# Franzininho.net
KiCad netlist of a schematic drawn in EAGLE
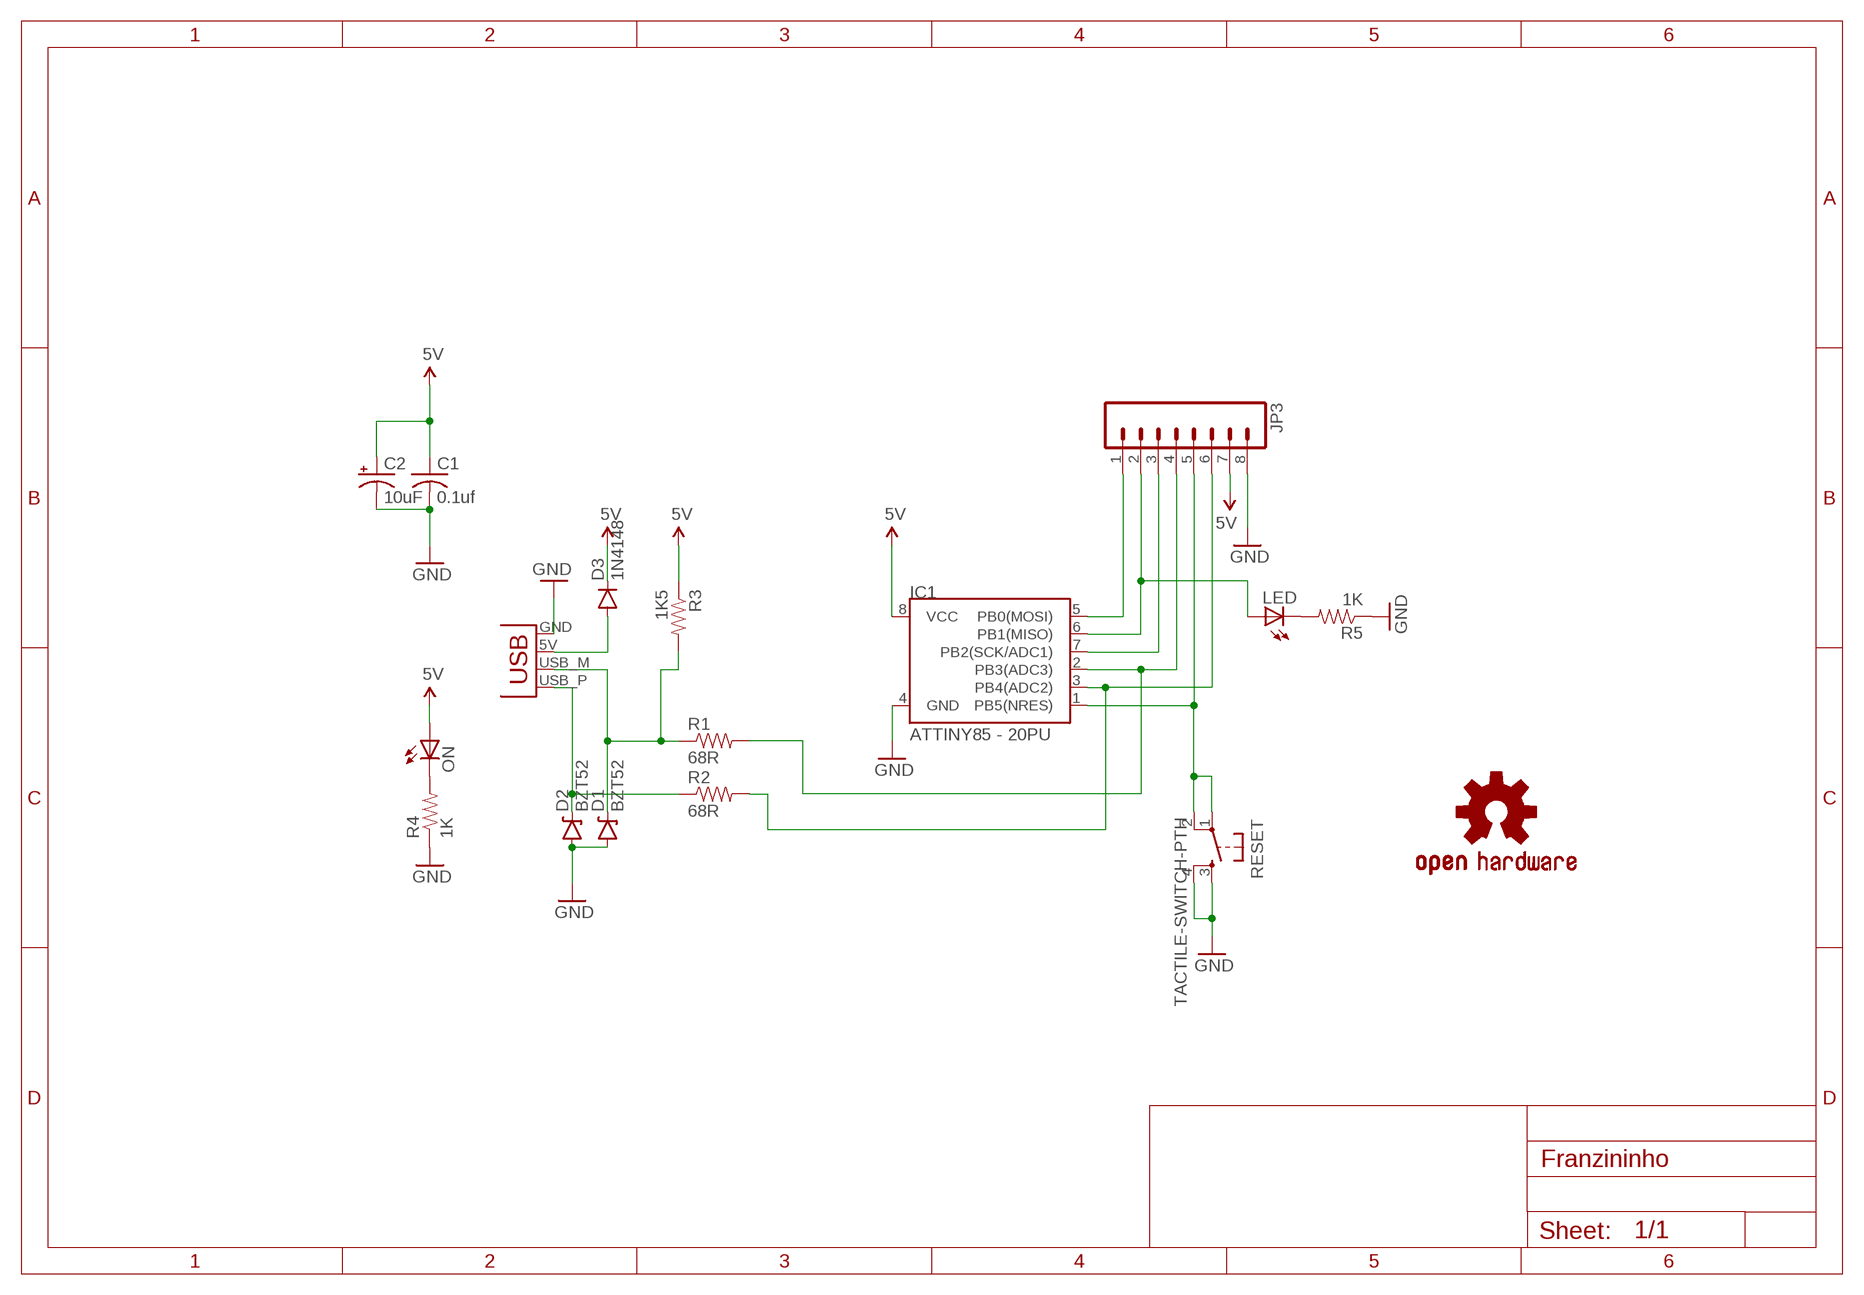
[diagram p0: schematic, sheet 1]

(export (version "E")
  (design (tool "Eeschema 10.0.6"))
  (components
    (comp (ref "C1")
      (value "0.1uf")
      (footprint "eagle-import:C025-025X050")
      (libsource (lib "eagle-import") (part "C-US025-025X050"))
    )
    (comp (ref "C2")
      (value "10uF")
      (footprint "eagle-import:E2,5-6E")
      (libsource (lib "eagle-import") (part "CPOL-USE2,5-6E"))
    )
    (comp (ref "D1")
      (value "BZT52")
      (footprint "eagle-import:DIODE-BZT52")
      (libsource (lib "eagle-import") (part "DIODE-ZENER"))
    )
    (comp (ref "D2")
      (value "BZT52")
      (footprint "eagle-import:DIODE-BZT52")
      (libsource (lib "eagle-import") (part "DIODE-ZENER"))
    )
    (comp (ref "D3")
      (value "1N4148")
      (footprint "eagle-import:DIODE-1N4148")
      (libsource (lib "eagle-import") (part "DIODE1N4148"))
    )
    (comp (ref "IC1")
      (value "ATTINY85 - 20PU")
      (footprint "eagle-import:DIP08")
      (libsource (lib "eagle-import") (part "ATTINY45TINY45-20-DIP"))
    )
    (comp (ref "JP3")
      (value "M08")
      (footprint "eagle-import:1X08_ROUND")
      (libsource (lib "eagle-import") (part "M08"))
    )
    (comp (ref "LED")
      (value "LED3MM")
      (footprint "eagle-import:LED3MM")
      (libsource (lib "eagle-import") (part "LED3MM"))
    )
    (comp (ref "LOGO1")
      (value "OSHW-LOGOL")
      (footprint "eagle-import:OSHW-LOGO-L")
      (libsource (lib "eagle-import") (part "OSHW-LOGOL"))
    )
    (comp (ref "ON")
      (value "LED3MM")
      (footprint "eagle-import:LED3MM")
      (libsource (lib "eagle-import") (part "LED3MM"))
    )
    (comp (ref "R1")
      (value "68R")
      (footprint "eagle-import:AXIAL-0.4")
      (libsource (lib "eagle-import") (part "RESISTORPTH-1/4W"))
    )
    (comp (ref "R2")
      (value "68R")
      (footprint "eagle-import:AXIAL-0.4")
      (libsource (lib "eagle-import") (part "RESISTORPTH-1/4W"))
    )
    (comp (ref "R3")
      (value "1K5")
      (footprint "eagle-import:AXIAL-0.4")
      (libsource (lib "eagle-import") (part "RESISTORPTH-1/4W"))
    )
    (comp (ref "R4")
      (value "1K")
      (footprint "eagle-import:AXIAL-0.4")
      (libsource (lib "eagle-import") (part "RESISTORPTH-1/4W"))
    )
    (comp (ref "R5")
      (value "1K")
      (footprint "eagle-import:AXIAL-0.4")
      (libsource (lib "eagle-import") (part "RESISTORPTH-1/4W"))
    )
    (comp (ref "RESET")
      (value "TACTILE-SWITCH-PTH")
      (footprint "eagle-import:TAC-SWITCH-PTH")
      (libsource (lib "eagle-import") (part "TACTILE-SWITCH-PTH"))
    )
    (comp (ref "X1")
      (value "USBPCB")
      (footprint "eagle-import:USB-A-PCB")
      (libsource (lib "eagle-import") (part "USBPCB"))
    )
  )
  (nets
    (net (code "1") (name "5V") (class "Default")
      (node (ref "C1") (pin "1") (pinfunction "1_1") (pintype "passive"))
      (node (ref "C2") (pin "+") (pinfunction "+_+") (pintype "passive"))
      (node (ref "D3") (pin "C") (pinfunction "C_C") (pintype "passive"))
      (node (ref "IC1") (pin "8") (pinfunction "VCC_8") (pintype "bidirectional"))
      (node (ref "JP3") (pin "7") (pinfunction "7_7") (pintype "passive"))
      (node (ref "ON") (pin "A") (pinfunction "A_A") (pintype "passive"))
      (node (ref "R3") (pin "P$1") (pinfunction "1_P$1") (pintype "passive"))
    )
    (net (code "2") (name "GND") (class "Default")
      (node (ref "C1") (pin "2") (pinfunction "2_2") (pintype "passive"))
      (node (ref "C2") (pin "-") (pinfunction "-_-") (pintype "passive"))
      (node (ref "D1") (pin "A") (pinfunction "A_A") (pintype "passive"))
      (node (ref "D2") (pin "A") (pinfunction "A_A") (pintype "passive"))
      (node (ref "IC1") (pin "4") (pinfunction "GND_4") (pintype "bidirectional"))
      (node (ref "JP3") (pin "8") (pinfunction "8_8") (pintype "passive"))
      (node (ref "R4") (pin "P$1") (pinfunction "1_P$1") (pintype "passive"))
      (node (ref "R5") (pin "P$1") (pinfunction "1_P$1") (pintype "passive"))
      (node (ref "RESET") (pin "3") (pinfunction "3_3") (pintype "passive"))
      (node (ref "RESET") (pin "4") (pinfunction "4_4") (pintype "passive"))
      (node (ref "X1") (pin "GND") (pinfunction "GND_GND") (pintype "bidirectional"))
    )
    (net (code "3") (name "Net-(IC1-PB0(MOSI))") (class "Default")
      (node (ref "IC1") (pin "5") (pinfunction "PB0(MOSI)_5") (pintype "bidirectional"))
      (node (ref "JP3") (pin "1") (pinfunction "1_1") (pintype "passive"))
    )
    (net (code "4") (name "Net-(IC1-PB1(MISO))") (class "Default")
      (node (ref "IC1") (pin "6") (pinfunction "PB1(MISO)_6") (pintype "bidirectional"))
      (node (ref "JP3") (pin "2") (pinfunction "2_2") (pintype "passive"))
      (node (ref "LED") (pin "A") (pinfunction "A_A") (pintype "passive"))
    )
    (net (code "5") (name "Net-(IC1-PB2(SCK{slash}ADC1))") (class "Default")
      (node (ref "IC1") (pin "7") (pinfunction "PB2(SCK/ADC1)_7") (pintype "bidirectional"))
      (node (ref "JP3") (pin "3") (pinfunction "3_3") (pintype "passive"))
    )
    (net (code "6") (name "Net-(IC1-PB3(ADC3))") (class "Default")
      (node (ref "IC1") (pin "2") (pinfunction "PB3(ADC3)_2") (pintype "bidirectional"))
      (node (ref "JP3") (pin "4") (pinfunction "4_4") (pintype "passive"))
      (node (ref "R1") (pin "P$2") (pinfunction "2_P$2") (pintype "passive"))
    )
    (net (code "7") (name "Net-(IC1-PB4(ADC2))") (class "Default")
      (node (ref "IC1") (pin "3") (pinfunction "PB4(ADC2)_3") (pintype "bidirectional"))
      (node (ref "JP3") (pin "6") (pinfunction "6_6") (pintype "passive"))
      (node (ref "R2") (pin "P$2") (pinfunction "2_P$2") (pintype "passive"))
    )
    (net (code "8") (name "Net-(IC1-PB5(NRES))") (class "Default")
      (node (ref "IC1") (pin "1") (pinfunction "PB5(NRES)_1") (pintype "bidirectional"))
      (node (ref "JP3") (pin "5") (pinfunction "5_5") (pintype "passive"))
      (node (ref "RESET") (pin "1") (pinfunction "1_1") (pintype "passive"))
      (node (ref "RESET") (pin "2") (pinfunction "2_2") (pintype "passive"))
    )
    (net (code "9") (name "Net-(LED-C)") (class "Default")
      (node (ref "LED") (pin "K") (pinfunction "C_K") (pintype "passive"))
      (node (ref "R5") (pin "P$2") (pinfunction "2_P$2") (pintype "passive"))
    )
    (net (code "10") (name "Net-(ON-C)") (class "Default")
      (node (ref "ON") (pin "K") (pinfunction "C_K") (pintype "passive"))
      (node (ref "R4") (pin "P$2") (pinfunction "2_P$2") (pintype "passive"))
    )
    (net (code "11") (name "Net-(R1-1)") (class "Default")
      (node (ref "D1") (pin "C") (pinfunction "C_C") (pintype "passive"))
      (node (ref "R1") (pin "P$1") (pinfunction "1_P$1") (pintype "passive"))
      (node (ref "R3") (pin "P$2") (pinfunction "2_P$2") (pintype "passive"))
      (node (ref "X1") (pin "USB_M") (pinfunction "D-_USB_M") (pintype "bidirectional"))
    )
    (net (code "12") (name "Net-(R2-1)") (class "Default")
      (node (ref "D2") (pin "C") (pinfunction "C_C") (pintype "passive"))
      (node (ref "R2") (pin "P$1") (pinfunction "1_P$1") (pintype "passive"))
      (node (ref "X1") (pin "USB_P") (pinfunction "D+_USB_P") (pintype "bidirectional"))
    )
    (net (code "13") (name "Net-(X1-VBUS)") (class "Default")
      (node (ref "D3") (pin "A") (pinfunction "A_A") (pintype "passive"))
      (node (ref "X1") (pin "5V") (pinfunction "VBUS_5V") (pintype "bidirectional"))
    )
  )
)
